# 5V_buck.net
KiCad netlist of a schematic drawn in Altium Designer
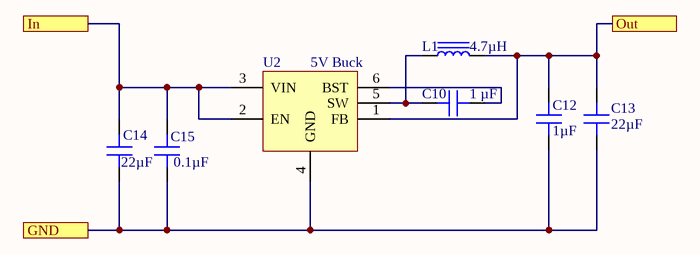
[diagram p0: 5V_buck.SchDoc]

(export (version "E")
  (design (tool "Eeschema 10.0.6"))
  (components
    (comp (ref "C10")
      (value "1 µF")
      (footprint "CAP 0402_1005")
      (description "CAP CER 0.1UF 16V X7R 0402")
      (fields (field (name "PART NUMBER") "C0402C104K4RACAUTO") (field (name "MANUFACTURER") "KEMET"))
      (libsource (lib "Celestial Altium Library - altium_library") (part "Capacitor"))
    )
    (comp (ref "C12")
      (value "1µF")
      (footprint "CAP 0603_1608")
      (description "CAP CER 1UF 25V X7R 0603")
      (fields
        (field (name "PART NUMBER") "GCJ188R71E105KA01D")
        (field (name "MANUFACTURER") "Murata Electronics")
      )
      (libsource (lib "Celestial Altium Library - altium_library") (part "Capacitor"))
    )
    (comp (ref "C13")
      (value "22µF")
      (footprint "CAP 0805_2012")
      (description "CAP CER 22UF 16V X5R 0805")
      (fields
        (field (name "PART NUMBER") "CL21A226MOQNNNE")
        (field (name "MANUFACTURER") "Samsung Electro-Mechanics")
      )
      (libsource (lib "Celestial Altium Library - altium_library") (part "Capacitor"))
    )
    (comp (ref "C14")
      (value "22µF")
      (footprint "CAP 0805_2012")
      (description "CAP CER 10UF 25V X7S 0805")
      (fields
        (field (name "PART NUMBER") "C2012X7S1E106K125AC")
        (field (name "MANUFACTURER") "TDK Corporation")
      )
      (libsource (lib "Celestial Altium Library - altium_library") (part "Capacitor"))
    )
    (comp (ref "C15")
      (value "0.1µF")
      (footprint "CAP 0603_1608")
      (description "CAP CER 0.1UF 100V 0603 EPOXY")
      (fields
        (field (name "PART NUMBER") "GCG188R92A104KA03D")
        (field (name "MANUFACTURER") "Murata Electronics")
      )
      (libsource (lib "Celestial Altium Library - altium_library") (part "Capacitor"))
    )
    (comp (ref "L1")
      (value "4.7µH")
      (footprint "IND 1008_2520")
      (description "FIXED IND 4.7UH 1A 110 MOHM SMD")
      (fields (field (name "PART NUMBER") "MLP2520S4R7ST0S1") (field (name "MANUFACTURER") "TDK Corporation"))
      (libsource (lib "Celestial Altium Library - altium_library") (part "Inductor"))
    )
    (comp (ref "U2")
      (value "5V Buck")
      (footprint "TSOT-26-6 - 3.2mm")
      (description "5V fixed step down Buck")
      (libsource (lib "IC") (part "AP63205WU-7"))
    )
  )
  (nets
    (net (code "1") (name "/GND") (class "Default")
      (node (ref "C12") (pin "1") (pinfunction "1_1") (pintype "passive"))
      (node (ref "C13") (pin "1") (pinfunction "1_1") (pintype "passive"))
      (node (ref "C14") (pin "1") (pinfunction "1_1") (pintype "passive"))
      (node (ref "C15") (pin "2") (pinfunction "2_2") (pintype "passive"))
      (node (ref "U2") (pin "4") (pinfunction "GND_4") (pintype "passive"))
    )
    (net (code "2") (name "/In") (class "Default")
      (node (ref "C14") (pin "2") (pinfunction "2_2") (pintype "passive"))
      (node (ref "C15") (pin "1") (pinfunction "1_1") (pintype "passive"))
      (node (ref "U2") (pin "2") (pinfunction "EN_2") (pintype "passive"))
      (node (ref "U2") (pin "3") (pinfunction "VIN_3") (pintype "passive"))
    )
    (net (code "3") (name "/Out") (class "Default")
      (node (ref "C12") (pin "2") (pinfunction "2_2") (pintype "passive"))
      (node (ref "C13") (pin "2") (pinfunction "2_2") (pintype "passive"))
      (node (ref "L1") (pin "2") (pinfunction "2_2") (pintype "passive"))
      (node (ref "U2") (pin "1") (pinfunction "FB_1") (pintype "passive"))
    )
    (net (code "4") (name "Net-(U2-BST)") (class "Default")
      (node (ref "C10") (pin "2") (pinfunction "2_2") (pintype "passive"))
      (node (ref "U2") (pin "6") (pinfunction "BST_6") (pintype "passive"))
    )
    (net (code "5") (name "Net-(U2-SW)") (class "Default")
      (node (ref "C10") (pin "1") (pinfunction "1_1") (pintype "passive"))
      (node (ref "L1") (pin "1") (pinfunction "1_1") (pintype "passive"))
      (node (ref "U2") (pin "5") (pinfunction "SW_5") (pintype "passive"))
    )
  )
)
